# RS232.net
KiCad netlist of a schematic drawn in Altium Designer
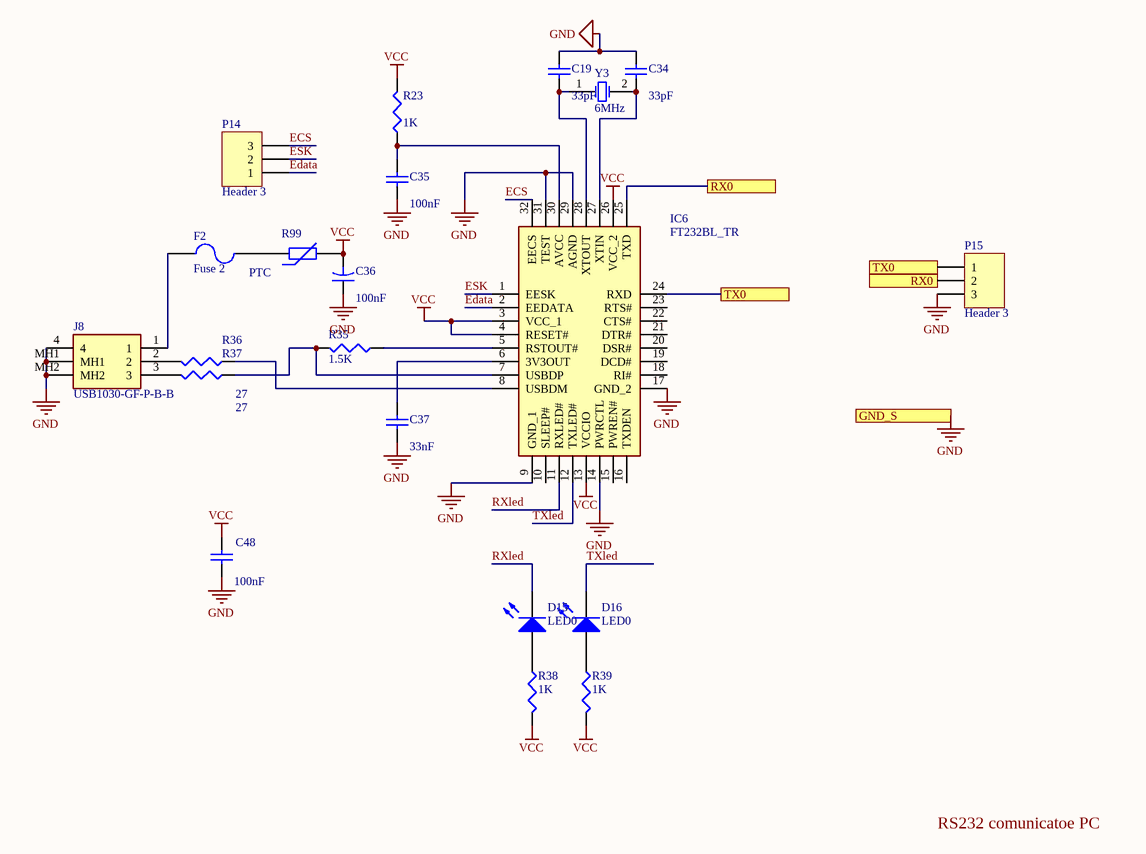
[diagram p0: RS232.SchDoc]

(export (version "E")
  (design (tool "Eeschema 10.0.6"))
  (components
    (comp (ref "C19")
      (value "33pF")
      (footprint "1206 CAP")
      (description "1206CAP 33pF")
      (fields (field (name "PUBLISHER") "Altium Limited"))
      (libsource (lib "Miscellaneous Devices") (part "Cap Semi"))
    )
    (comp (ref "C34")
      (value "33pF")
      (footprint "1206 CAP")
      (description "1206CAP 33pF")
      (fields (field (name "PUBLISHER") "Altium Limited"))
      (libsource (lib "Miscellaneous Devices") (part "Cap Semi"))
    )
    (comp (ref "C35")
      (value "100nF")
      (footprint "1206 CAP")
      (description "1206CAP 100nF")
      (fields (field (name "PUBLISHER") "Altium Limited"))
      (libsource (lib "Miscellaneous Devices") (part "Cap Semi"))
    )
    (comp (ref "C36")
      (value "100nF")
      (footprint "TH polarized 5mm")
      (description "polarized cap 5mm pitch")
      (fields (field (name "PUBLISHER") "Altium Limited"))
      (libsource (lib "Miscellaneous Devices") (part "Cap2"))
    )
    (comp (ref "C37")
      (value "33nF")
      (footprint "1206 CAP")
      (description "1206CAP 33nF")
      (fields (field (name "PUBLISHER") "Altium Limited"))
      (libsource (lib "Miscellaneous Devices") (part "Cap Semi"))
    )
    (comp (ref "C48")
      (value "100nF")
      (footprint "1206 CAP")
      (description "1206CAP 100nF")
      (fields (field (name "PUBLISHER") "Altium Limited"))
      (libsource (lib "Miscellaneous Devices") (part "Cap Semi"))
    )
    (comp (ref "D15")
      (value "LED0")
      (footprint "Miscellaneous Devices:6-0805_L")
      (description "Typical INFRARED GaAs LED")
      (fields (field (name "PUBLISHER") "Altium Limited"))
      (libsource (lib "Miscellaneous Devices") (part "LED0"))
    )
    (comp (ref "D16")
      (value "LED0")
      (footprint "Miscellaneous Devices:6-0805_L")
      (description "Typical INFRARED GaAs LED")
      (fields (field (name "PUBLISHER") "Altium Limited"))
      (libsource (lib "Miscellaneous Devices") (part "LED0"))
    )
    (comp (ref "F2")
      (value "Fuse 2")
      (footprint "THROUGH HOLE 5mm")
      (description "Fuse")
      (fields (field (name "PUBLISHER") "Altium Limited"))
      (libsource (lib "Miscellaneous Devices") (part "Fuse 2"))
    )
    (comp (ref "IC6")
      (value "FT232BL_TR")
      (footprint "SamacSys:QFP80P900X900X160-32N")
      (description "Integrated Circuit")
      (fields (field (name "MANUFACTURER_PART_NUMBER") "FT232BL/TR"))
      (libsource (lib "*") (part "FT232BL_TR"))
    )
    (comp (ref "J8")
      (value "USB1030-GF-P-B-B")
      (footprint "SamacSys:USB1030GFPBB")
      (description "Connector")
      (fields (field (name "MOUSER PART NUMBER") "640-USB1030-GF-P-B-B"))
      (libsource (lib "*") (part "USB1030-GF-P-B-B"))
    )
    (comp (ref "P14")
      (value "Header 3")
      (footprint "HDR1X3")
      (description "Header, 3-Pin")
      (fields (field (name "PUBLISHER") "Altium Limited"))
      (libsource (lib "Miscellaneous Connectors") (part "Header 3"))
    )
    (comp (ref "P15")
      (value "Header 3")
      (footprint "HDR1X3")
      (description "Header, 3-Pin")
      (fields (field (name "PUBLISHER") "Altium Limited"))
      (libsource (lib "") (part "Header 3_1"))
    )
    (comp (ref "R23")
      (value "1K")
      (footprint "0805")
      (description "0805RES 1K")
      (fields (field (name "PUBLISHER") "Altium Limited"))
      (libsource (lib "Miscellaneous Devices") (part "Res3"))
    )
    (comp (ref "R35")
      (value "1.5K")
      (footprint "1206 CAP")
      (description "1206RES 1K5")
      (fields (field (name "PUBLISHER") "Altium Limited"))
      (libsource (lib "Miscellaneous Devices") (part "Res3"))
    )
    (comp (ref "R36")
      (value "27")
      (footprint "1206 CAP")
      (description "1206RES 27 OHM")
      (fields (field (name "PUBLISHER") "Altium Limited"))
      (libsource (lib "Miscellaneous Devices") (part "Res3"))
    )
    (comp (ref "R37")
      (value "27")
      (footprint "1206 CAP")
      (description "1206RES 27 OHM")
      (fields (field (name "PUBLISHER") "Altium Limited"))
      (libsource (lib "Miscellaneous Devices") (part "Res3"))
    )
    (comp (ref "R38")
      (value "1K")
      (footprint "J1-0603")
      (description "0603RES 1K")
      (fields (field (name "PUBLISHER") "Altium Limited"))
      (libsource (lib "Miscellaneous Devices") (part "Res3"))
    )
    (comp (ref "R39")
      (value "1K")
      (footprint "J1-0603")
      (description "0603RES 1K")
      (fields (field (name "PUBLISHER") "Altium Limited"))
      (libsource (lib "Miscellaneous Devices") (part "Res3"))
    )
    (comp (ref "R99")
      (value "PTC")
      (footprint "Miscellaneous Devices:R38")
      (description "Varistor (Voltage-Sensitive Resistor)")
      (fields (field (name "PUBLISHER") "Altium Limited"))
      (libsource (lib "Miscellaneous Devices") (part "Res Varistor"))
    )
    (comp (ref "Y3")
      (value "6MHz")
      (footprint "Miscellaneous Devices:RAD-0.2")
      (description "Crystal Oscillator")
      (fields (field (name "PUBLISHER") "Altium Limited"))
      (libsource (lib "Miscellaneous Devices") (part "XTAL"))
    )
  )
  (nets
    (net (code "1") (name "/ECS") (class "Default")
      (node (ref "IC6") (pin "32") (pinfunction "EECS_32") (pintype "passive"))
      (node (ref "P14") (pin "3") (pinfunction "3_3") (pintype "passive"))
    )
    (net (code "2") (name "/ESK") (class "Default")
      (node (ref "IC6") (pin "1") (pinfunction "EESK_1") (pintype "passive"))
      (node (ref "P14") (pin "2") (pinfunction "2_2") (pintype "passive"))
    )
    (net (code "3") (name "/Edata") (class "Default")
      (node (ref "IC6") (pin "2") (pinfunction "EEDATA_2") (pintype "passive"))
      (node (ref "P14") (pin "1") (pinfunction "1_1") (pintype "passive"))
    )
    (net (code "4") (name "/RX0") (class "Default")
      (node (ref "IC6") (pin "25") (pinfunction "TXD_25") (pintype "passive"))
      (node (ref "P15") (pin "2") (pinfunction "2_2") (pintype "passive"))
    )
    (net (code "5") (name "/RXled") (class "Default")
      (node (ref "D15") (pin "2") (pinfunction "K_2") (pintype "passive"))
      (node (ref "IC6") (pin "11") (pinfunction "RXLED#_11") (pintype "passive"))
    )
    (net (code "6") (name "/TX0") (class "Default")
      (node (ref "IC6") (pin "24") (pinfunction "RXD_24") (pintype "passive"))
      (node (ref "P15") (pin "1") (pinfunction "1_1") (pintype "passive"))
    )
    (net (code "7") (name "/TXled") (class "Default")
      (node (ref "D16") (pin "2") (pinfunction "K_2") (pintype "passive"))
      (node (ref "IC6") (pin "12") (pinfunction "TXLED#_12") (pintype "passive"))
    )
    (net (code "8") (name "GND") (class "Default")
      (node (ref "C19") (pin "1") (pinfunction "1_1") (pintype "passive"))
      (node (ref "C34") (pin "1") (pinfunction "1_1") (pintype "passive"))
      (node (ref "C35") (pin "1") (pinfunction "1_1") (pintype "passive"))
      (node (ref "C36") (pin "1") (pinfunction "1_1") (pintype "passive"))
      (node (ref "C37") (pin "1") (pinfunction "1_1") (pintype "passive"))
      (node (ref "C48") (pin "1") (pinfunction "1_1") (pintype "passive"))
      (node (ref "IC6") (pin "14") (pinfunction "PWRCTL_14") (pintype "passive"))
      (node (ref "IC6") (pin "17") (pinfunction "GND_2_17") (pintype "passive"))
      (node (ref "IC6") (pin "29") (pinfunction "AGND_29") (pintype "passive"))
      (node (ref "IC6") (pin "31") (pinfunction "TEST_31") (pintype "passive"))
      (node (ref "IC6") (pin "9") (pinfunction "GND_1_9") (pintype "passive"))
      (node (ref "J8") (pin "4") (pinfunction "4_4") (pintype "passive"))
      (node (ref "J8") (pin "MH1") (pinfunction "MH1_MH1") (pintype "passive"))
      (node (ref "J8") (pin "MH2") (pinfunction "MH2_MH2") (pintype "passive"))
      (node (ref "P15") (pin "3") (pinfunction "3_3") (pintype "passive"))
    )
    (net (code "9") (name "Net-(D15-A)") (class "Default")
      (node (ref "D15") (pin "1") (pinfunction "A_1") (pintype "passive"))
      (node (ref "R38") (pin "1") (pinfunction "1_1") (pintype "passive"))
    )
    (net (code "10") (name "Net-(D16-A)") (class "Default")
      (node (ref "D16") (pin "1") (pinfunction "A_1") (pintype "passive"))
      (node (ref "R39") (pin "1") (pinfunction "1_1") (pintype "passive"))
    )
    (net (code "11") (name "Net-(F2-Pad1)") (class "Default")
      (node (ref "F2") (pin "1") (pinfunction "1_1") (pintype "passive"))
      (node (ref "J8") (pin "1") (pinfunction "1_1") (pintype "passive"))
    )
    (net (code "12") (name "Net-(F2-Pad2)") (class "Default")
      (node (ref "F2") (pin "2") (pinfunction "2_2") (pintype "passive"))
      (node (ref "R99") (pin "1") (pinfunction "1_1") (pintype "passive"))
    )
    (net (code "13") (name "Net-(IC6-3V3OUT)") (class "Default")
      (node (ref "C37") (pin "2") (pinfunction "2_2") (pintype "passive"))
      (node (ref "IC6") (pin "6") (pinfunction "3V3OUT_6") (pintype "passive"))
    )
    (net (code "14") (name "Net-(IC6-AVCC)") (class "Default")
      (node (ref "C35") (pin "2") (pinfunction "2_2") (pintype "passive"))
      (node (ref "IC6") (pin "30") (pinfunction "AVCC_30") (pintype "passive"))
      (node (ref "R23") (pin "1") (pinfunction "1_1") (pintype "passive"))
    )
    (net (code "15") (name "Net-(IC6-RSTOUT#)") (class "Default")
      (node (ref "IC6") (pin "5") (pinfunction "RSTOUT#_5") (pintype "passive"))
      (node (ref "R35") (pin "1") (pinfunction "1_1") (pintype "passive"))
    )
    (net (code "16") (name "Net-(IC6-USBDM)") (class "Default")
      (node (ref "IC6") (pin "8") (pinfunction "USBDM_8") (pintype "passive"))
      (node (ref "R36") (pin "1") (pinfunction "1_1") (pintype "passive"))
    )
    (net (code "17") (name "Net-(IC6-USBDP)") (class "Default")
      (node (ref "IC6") (pin "7") (pinfunction "USBDP_7") (pintype "passive"))
      (node (ref "R35") (pin "2") (pinfunction "2_2") (pintype "passive"))
      (node (ref "R37") (pin "1") (pinfunction "1_1") (pintype "passive"))
    )
    (net (code "18") (name "Net-(IC6-XTIN)") (class "Default")
      (node (ref "C34") (pin "2") (pinfunction "2_2") (pintype "passive"))
      (node (ref "IC6") (pin "27") (pinfunction "XTIN_27") (pintype "passive"))
      (node (ref "Y3") (pin "2") (pinfunction "OSC2_2") (pintype "passive"))
    )
    (net (code "19") (name "Net-(IC6-XTOUT)") (class "Default")
      (node (ref "C19") (pin "2") (pinfunction "2_2") (pintype "passive"))
      (node (ref "IC6") (pin "28") (pinfunction "XTOUT_28") (pintype "passive"))
      (node (ref "Y3") (pin "1") (pinfunction "OSC1_1") (pintype "passive"))
    )
    (net (code "20") (name "Net-(J8-Pad2)") (class "Default")
      (node (ref "J8") (pin "2") (pinfunction "2_2") (pintype "passive"))
      (node (ref "R36") (pin "2") (pinfunction "2_2") (pintype "passive"))
    )
    (net (code "21") (name "Net-(J8-Pad3)") (class "Default")
      (node (ref "J8") (pin "3") (pinfunction "3_3") (pintype "passive"))
      (node (ref "R37") (pin "2") (pinfunction "2_2") (pintype "passive"))
    )
    (net (code "22") (name "VCC") (class "Default")
      (node (ref "C36") (pin "2") (pinfunction "2_2") (pintype "passive"))
      (node (ref "C48") (pin "2") (pinfunction "2_2") (pintype "passive"))
      (node (ref "IC6") (pin "13") (pinfunction "VCCIO_13") (pintype "passive"))
      (node (ref "IC6") (pin "26") (pinfunction "VCC_2_26") (pintype "passive"))
      (node (ref "IC6") (pin "3") (pinfunction "VCC_1_3") (pintype "passive"))
      (node (ref "IC6") (pin "4") (pinfunction "RESET#_4") (pintype "passive"))
      (node (ref "R23") (pin "2") (pinfunction "2_2") (pintype "passive"))
      (node (ref "R38") (pin "2") (pinfunction "2_2") (pintype "passive"))
      (node (ref "R39") (pin "2") (pinfunction "2_2") (pintype "passive"))
      (node (ref "R99") (pin "2") (pinfunction "2_2") (pintype "passive"))
    )
    (net (code "23") (name "unconnected-(IC6-CTS#-Pad22)") (class "Default")
      (node (ref "IC6") (pin "22") (pinfunction "CTS#_22") (pintype "passive"))
    )
    (net (code "24") (name "unconnected-(IC6-DCD#-Pad19)") (class "Default")
      (node (ref "IC6") (pin "19") (pinfunction "DCD#_19") (pintype "passive"))
    )
    (net (code "25") (name "unconnected-(IC6-DSR#-Pad20)") (class "Default")
      (node (ref "IC6") (pin "20") (pinfunction "DSR#_20") (pintype "passive"))
    )
    (net (code "26") (name "unconnected-(IC6-DTR#-Pad21)") (class "Default")
      (node (ref "IC6") (pin "21") (pinfunction "DTR#_21") (pintype "passive"))
    )
    (net (code "27") (name "unconnected-(IC6-PWREN#-Pad15)") (class "Default")
      (node (ref "IC6") (pin "15") (pinfunction "PWREN#_15") (pintype "passive"))
    )
    (net (code "28") (name "unconnected-(IC6-RI#-Pad18)") (class "Default")
      (node (ref "IC6") (pin "18") (pinfunction "RI#_18") (pintype "passive"))
    )
    (net (code "29") (name "unconnected-(IC6-RTS#-Pad23)") (class "Default")
      (node (ref "IC6") (pin "23") (pinfunction "RTS#_23") (pintype "passive"))
    )
    (net (code "30") (name "unconnected-(IC6-SLEEP#-Pad10)") (class "Default")
      (node (ref "IC6") (pin "10") (pinfunction "SLEEP#_10") (pintype "passive"))
    )
    (net (code "31") (name "unconnected-(IC6-TXDEN-Pad16)") (class "Default")
      (node (ref "IC6") (pin "16") (pinfunction "TXDEN_16") (pintype "passive"))
    )
  )
)
